# Sheet1.net
KiCad netlist of a schematic drawn in Altium Designer
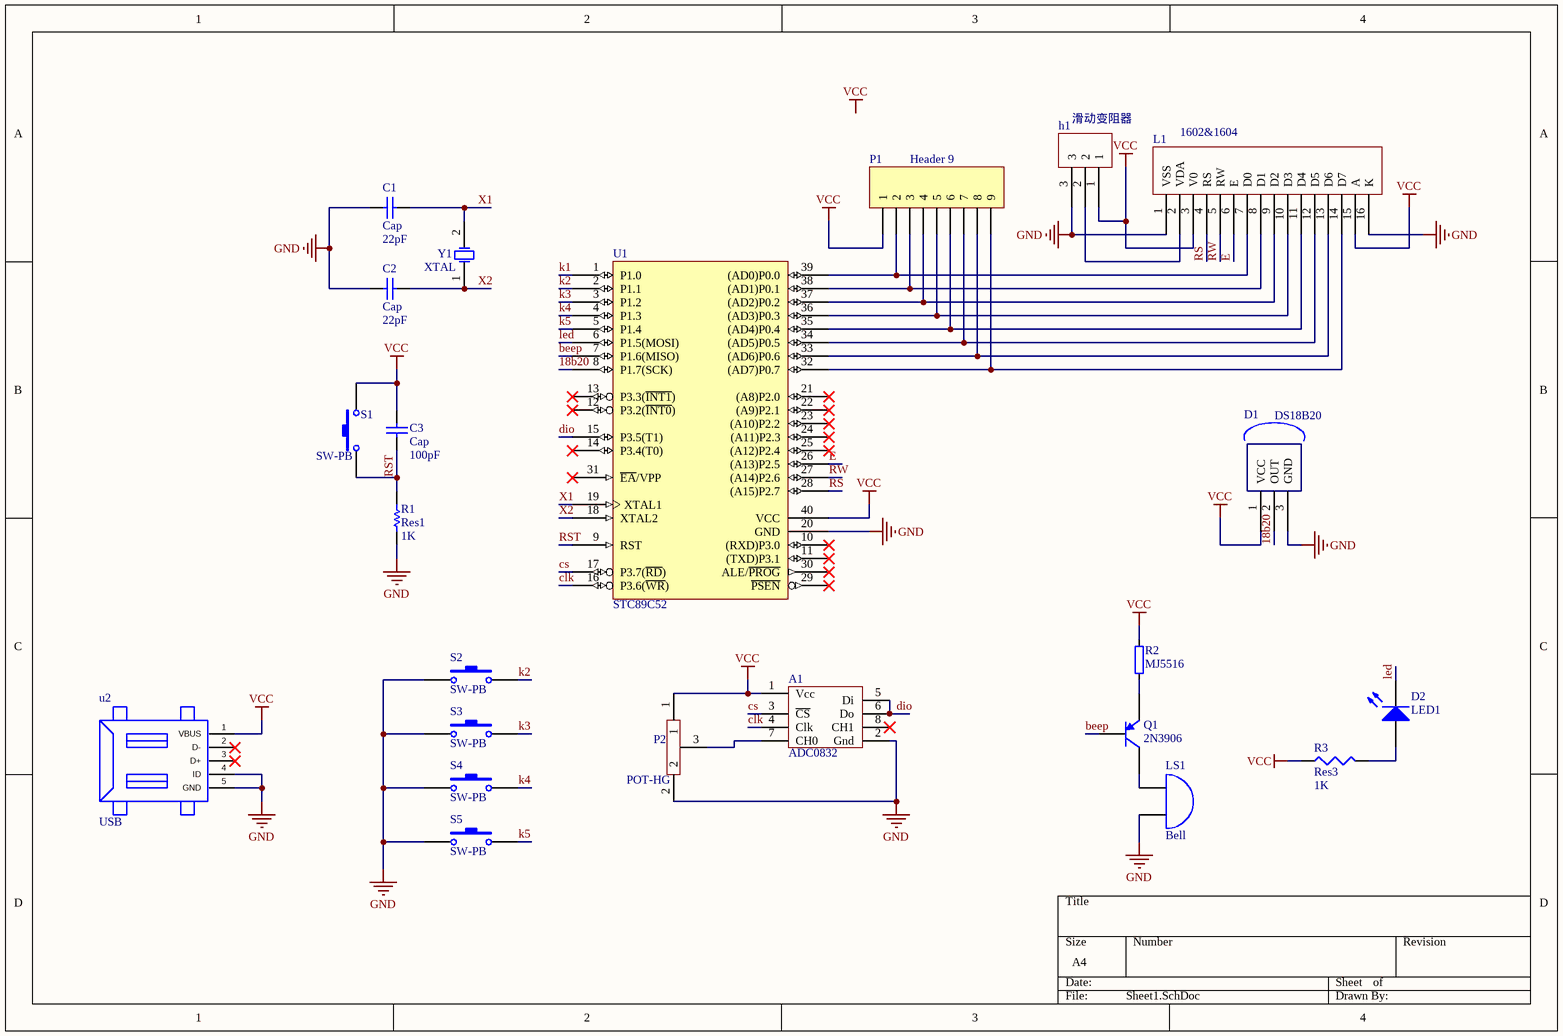
[diagram p0: Sheet1.SchDoc]

(export (version "E")
  (design (tool "Eeschema 10.0.6"))
  (components
    (comp (ref "A1") (value "ADC0832") (libsource (lib "mine") (part "ADC0832")))
    (comp (ref "C1")
      (value "Cap")
      (footprint "RAD-0.3")
      (description "Capacitor")
      (fields (field (name "ALTIUM_VALUE") "22pF") (field (name "PUBLISHER") "Altium Limited"))
      (libsource (lib "Miscellaneous Devices") (part "Cap"))
    )
    (comp (ref "C2")
      (value "Cap")
      (footprint "RAD-0.3")
      (description "Capacitor")
      (fields (field (name "ALTIUM_VALUE") "22pF") (field (name "PUBLISHER") "Altium Limited"))
      (libsource (lib "Miscellaneous Devices") (part "Cap"))
    )
    (comp (ref "C3")
      (value "Cap")
      (footprint "RAD-0.3")
      (description "Capacitor")
      (fields (field (name "ALTIUM_VALUE") "100pF") (field (name "PUBLISHER") "Altium Limited"))
      (libsource (lib "Miscellaneous Devices") (part "Cap"))
    )
    (comp (ref "D1") (value "DS18B20") (libsource (lib "mine") (part "DS18B20")))
    (comp (ref "D2")
      (value "LED1")
      (footprint "LED-1")
      (description "Typical RED GaAs LED")
      (fields (field (name "PUBLISHER") "Altium Limited"))
      (libsource (lib "Miscellaneous Devices") (part "LED1"))
    )
    (comp (ref "h1") (value "滑动变阻器") (libsource (lib "mine") (part "滑动变阻器")))
    (comp (ref "L1") (value "1602&1604") (libsource (lib "mine") (part "1602&1604")))
    (comp (ref "LS1")
      (value "Bell")
      (footprint "PIN2")
      (description "Electrical Bell")
      (fields (field (name "PUBLISHER") "Altium Limited"))
      (libsource (lib "Miscellaneous Devices") (part "Bell"))
    )
    (comp (ref "P1")
      (value "Header 9")
      (footprint "HDR1X9")
      (description "Header, 9-Pin")
      (fields (field (name "PUBLISHER") "Altium Limited"))
      (libsource (lib "Miscellaneous Connectors") (part "Header 9"))
    )
    (comp (ref "P2") (value "POT-HG") (libsource (lib "mine") (part "POT-HG")))
    (comp (ref "Q1")
      (value "2N3906")
      (footprint "TO-92A")
      (description "PNP General Purpose Amplifier")
      (fields (field (name "PUBLISHER") "Altium Limited"))
      (libsource (lib "Miscellaneous Devices") (part "2N3906"))
    )
    (comp (ref "R1")
      (value "Res1")
      (footprint "AXIAL-0.3")
      (description "Resistor")
      (fields (field (name "ALTIUM_VALUE") "1K") (field (name "PUBLISHER") "Altium Limited"))
      (libsource (lib "Miscellaneous Devices") (part "Res1"))
    )
    (comp (ref "R2")
      (value "MJ5516")
      (footprint "MJ5515")
      (description "CR-MJ5516")
      (libsource (lib "常用器件") (part "MJ5516"))
    )
    (comp (ref "R3")
      (value "Res3")
      (footprint "J1-0603")
      (description "Resistor")
      (fields (field (name "ALTIUM_VALUE") "1K") (field (name "PUBLISHER") "Altium Limited"))
      (libsource (lib "Miscellaneous Devices") (part "Res3"))
    )
    (comp (ref "S1")
      (value "SW-PB")
      (footprint "SPST-2")
      (description "Switch")
      (fields (field (name "PUBLISHER") "Altium Limited"))
      (libsource (lib "Miscellaneous Devices") (part "SW-PB"))
    )
    (comp (ref "S2")
      (value "SW-PB")
      (footprint "SPST-2")
      (description "Switch")
      (fields (field (name "PUBLISHER") "Altium Limited"))
      (libsource (lib "常用器件") (part "SW-PB"))
    )
    (comp (ref "S3")
      (value "SW-PB")
      (footprint "SPST-2")
      (description "Switch")
      (fields (field (name "PUBLISHER") "Altium Limited"))
      (libsource (lib "常用器件") (part "SW-PB"))
    )
    (comp (ref "S4")
      (value "SW-PB")
      (footprint "SPST-2")
      (description "Switch")
      (fields (field (name "PUBLISHER") "Altium Limited"))
      (libsource (lib "常用器件") (part "SW-PB"))
    )
    (comp (ref "S5")
      (value "SW-PB")
      (footprint "SPST-2")
      (description "Switch")
      (fields (field (name "PUBLISHER") "Altium Limited"))
      (libsource (lib "常用器件") (part "SW-PB"))
    )
    (comp (ref "U1")
      (value "STC89C52")
      (footprint "DIP-40")
      (description "8-Bit Microcontroller with 4K ISP Flash ROM")
      (libsource (lib "单片机8051") (part "AT89S51"))
    )
    (comp (ref "u2") (value "USB") (libsource (lib "mine") (part "USB")))
    (comp (ref "Y1")
      (value "XTAL")
      (footprint "R38")
      (description "Crystal Oscillator")
      (fields (field (name "PUBLISHER") "Altium Limited"))
      (libsource (lib "Miscellaneous Devices") (part "XTAL"))
    )
  )
  (nets
    (net (code "1") (name "/18b20") (class "Default")
      (node (ref "D1") (pin "2") (pinfunction "OUT_2") (pintype "passive"))
      (node (ref "U1") (pin "8") (pinfunction "P1.7(SCK)_8") (pintype "bidirectional"))
    )
    (net (code "2") (name "/E") (class "Default")
      (node (ref "L1") (pin "6") (pinfunction "E_6") (pintype "passive"))
      (node (ref "U1") (pin "26") (pinfunction "(A13)P2.5_26") (pintype "bidirectional"))
    )
    (net (code "3") (name "/RS") (class "Default")
      (node (ref "L1") (pin "4") (pinfunction "RS_4") (pintype "passive"))
      (node (ref "U1") (pin "28") (pinfunction "(A15)P2.7_28") (pintype "bidirectional"))
    )
    (net (code "4") (name "/RST") (class "Default")
      (node (ref "C3") (pin "1") (pinfunction "1_1") (pintype "passive"))
      (node (ref "R1") (pin "2") (pinfunction "2_2") (pintype "passive"))
      (node (ref "S1") (pin "1") (pinfunction "1_1") (pintype "passive"))
      (node (ref "U1") (pin "9") (pinfunction "RST_9") (pintype "input"))
    )
    (net (code "5") (name "/RW") (class "Default")
      (node (ref "L1") (pin "5") (pinfunction "RW_5") (pintype "passive"))
      (node (ref "U1") (pin "27") (pinfunction "(A14)P2.6_27") (pintype "bidirectional"))
    )
    (net (code "6") (name "/X1") (class "Default")
      (node (ref "C1") (pin "2") (pinfunction "2_2") (pintype "passive"))
      (node (ref "U1") (pin "19") (pinfunction "XTAL1_19") (pintype "input"))
      (node (ref "Y1") (pin "2") (pinfunction "OSC2_2") (pintype "passive"))
    )
    (net (code "7") (name "/X2") (class "Default")
      (node (ref "C2") (pin "2") (pinfunction "2_2") (pintype "passive"))
      (node (ref "U1") (pin "18") (pinfunction "XTAL2_18") (pintype "input"))
      (node (ref "Y1") (pin "1") (pinfunction "OSC1_1") (pintype "passive"))
    )
    (net (code "8") (name "/beep") (class "Default")
      (node (ref "Q1") (pin "2") (pinfunction "B_2") (pintype "passive"))
      (node (ref "U1") (pin "7") (pinfunction "P1.6(MISO)_7") (pintype "bidirectional"))
    )
    (net (code "9") (name "/clk") (class "Default")
      (node (ref "A1") (pin "4") (pinfunction "Clk_4") (pintype "passive"))
      (node (ref "U1") (pin "16") (pinfunction "P3.6(~{WR})_16") (pintype "bidirectional"))
    )
    (net (code "10") (name "/cs") (class "Default")
      (node (ref "A1") (pin "3") (pinfunction "~{CS}_3") (pintype "passive"))
      (node (ref "U1") (pin "17") (pinfunction "P3.7(~{RD})_17") (pintype "bidirectional"))
    )
    (net (code "11") (name "/dio") (class "Default")
      (node (ref "A1") (pin "5") (pinfunction "Di_5") (pintype "passive"))
      (node (ref "A1") (pin "6") (pinfunction "Do_6") (pintype "passive"))
      (node (ref "U1") (pin "15") (pinfunction "P3.5(T1)_15") (pintype "bidirectional"))
    )
    (net (code "12") (name "/k1") (class "Default")
      (node (ref "U1") (pin "1") (pinfunction "P1.0_1") (pintype "bidirectional"))
    )
    (net (code "13") (name "/k2") (class "Default")
      (node (ref "S2") (pin "2") (pinfunction "2_2") (pintype "passive"))
      (node (ref "U1") (pin "2") (pinfunction "P1.1_2") (pintype "bidirectional"))
    )
    (net (code "14") (name "/k3") (class "Default")
      (node (ref "S3") (pin "2") (pinfunction "2_2") (pintype "passive"))
      (node (ref "U1") (pin "3") (pinfunction "P1.2_3") (pintype "bidirectional"))
    )
    (net (code "15") (name "/k4") (class "Default")
      (node (ref "S4") (pin "2") (pinfunction "2_2") (pintype "passive"))
      (node (ref "U1") (pin "4") (pinfunction "P1.3_4") (pintype "bidirectional"))
    )
    (net (code "16") (name "/k5") (class "Default")
      (node (ref "S5") (pin "2") (pinfunction "2_2") (pintype "passive"))
      (node (ref "U1") (pin "5") (pinfunction "P1.4_5") (pintype "bidirectional"))
    )
    (net (code "17") (name "/led") (class "Default")
      (node (ref "D2") (pin "2") (pinfunction "K_2") (pintype "passive"))
      (node (ref "U1") (pin "6") (pinfunction "P1.5(MOSI)_6") (pintype "bidirectional"))
    )
    (net (code "18") (name "GND") (class "Default")
      (node (ref "A1") (pin "2") (pinfunction "Gnd_2") (pintype "passive"))
      (node (ref "C1") (pin "1") (pinfunction "1_1") (pintype "passive"))
      (node (ref "C2") (pin "1") (pinfunction "1_1") (pintype "passive"))
      (node (ref "D1") (pin "3") (pinfunction "GND_3") (pintype "passive"))
      (node (ref "L1") (pin "1") (pinfunction "VSS_1") (pintype "passive"))
      (node (ref "L1") (pin "16") (pinfunction "K_16") (pintype "passive"))
      (node (ref "LS1") (pin "2") (pinfunction "B_2") (pintype "passive"))
      (node (ref "P2") (pin "2") (pinfunction "2_2") (pintype "passive"))
      (node (ref "R1") (pin "1") (pinfunction "1_1") (pintype "passive"))
      (node (ref "S2") (pin "1") (pinfunction "1_1") (pintype "passive"))
      (node (ref "S3") (pin "1") (pinfunction "1_1") (pintype "passive"))
      (node (ref "S4") (pin "1") (pinfunction "1_1") (pintype "passive"))
      (node (ref "S5") (pin "1") (pinfunction "1_1") (pintype "passive"))
      (node (ref "U1") (pin "20") (pinfunction "GND_20") (pintype "power_in"))
      (node (ref "h1") (pin "3") (pinfunction "3_3") (pintype "passive"))
      (node (ref "u2") (pin "4") (pinfunction "ID_4") (pintype "passive"))
      (node (ref "u2") (pin "5") (pinfunction "GND_5") (pintype "passive"))
    )
    (net (code "19") (name "Net-(A1-CH0)") (class "Default")
      (node (ref "A1") (pin "7") (pinfunction "CH0_7") (pintype "passive"))
      (node (ref "P2") (pin "3") (pintype "passive"))
    )
    (net (code "20") (name "Net-(D2-A)") (class "Default")
      (node (ref "D2") (pin "1") (pinfunction "A_1") (pintype "passive"))
      (node (ref "R3") (pin "2") (pinfunction "2_2") (pintype "passive"))
    )
    (net (code "21") (name "Net-(L1-D0)") (class "Default")
      (node (ref "L1") (pin "7") (pinfunction "D0_7") (pintype "passive"))
      (node (ref "P1") (pin "2") (pinfunction "2_2") (pintype "passive"))
      (node (ref "U1") (pin "39") (pinfunction "(AD0)P0.0_39") (pintype "bidirectional"))
    )
    (net (code "22") (name "Net-(L1-D1)") (class "Default")
      (node (ref "L1") (pin "8") (pinfunction "D1_8") (pintype "passive"))
      (node (ref "P1") (pin "3") (pinfunction "3_3") (pintype "passive"))
      (node (ref "U1") (pin "38") (pinfunction "(AD1)P0.1_38") (pintype "bidirectional"))
    )
    (net (code "23") (name "Net-(L1-D2)") (class "Default")
      (node (ref "L1") (pin "9") (pinfunction "D2_9") (pintype "passive"))
      (node (ref "P1") (pin "4") (pinfunction "4_4") (pintype "passive"))
      (node (ref "U1") (pin "37") (pinfunction "(AD2)P0.2_37") (pintype "bidirectional"))
    )
    (net (code "24") (name "Net-(L1-D3)") (class "Default")
      (node (ref "L1") (pin "10") (pinfunction "D3_10") (pintype "passive"))
      (node (ref "P1") (pin "5") (pinfunction "5_5") (pintype "passive"))
      (node (ref "U1") (pin "36") (pinfunction "(AD3)P0.3_36") (pintype "bidirectional"))
    )
    (net (code "25") (name "Net-(L1-D4)") (class "Default")
      (node (ref "L1") (pin "11") (pinfunction "D4_11") (pintype "passive"))
      (node (ref "P1") (pin "6") (pinfunction "6_6") (pintype "passive"))
      (node (ref "U1") (pin "35") (pinfunction "(AD4)P0.4_35") (pintype "bidirectional"))
    )
    (net (code "26") (name "Net-(L1-D5)") (class "Default")
      (node (ref "L1") (pin "12") (pinfunction "D5_12") (pintype "passive"))
      (node (ref "P1") (pin "7") (pinfunction "7_7") (pintype "passive"))
      (node (ref "U1") (pin "34") (pinfunction "(AD5)P0.5_34") (pintype "bidirectional"))
    )
    (net (code "27") (name "Net-(L1-D6)") (class "Default")
      (node (ref "L1") (pin "13") (pinfunction "D6_13") (pintype "passive"))
      (node (ref "P1") (pin "8") (pinfunction "8_8") (pintype "passive"))
      (node (ref "U1") (pin "33") (pinfunction "(AD6)P0.6_33") (pintype "bidirectional"))
    )
    (net (code "28") (name "Net-(L1-D7)") (class "Default")
      (node (ref "L1") (pin "14") (pinfunction "D7_14") (pintype "passive"))
      (node (ref "P1") (pin "9") (pinfunction "9_9") (pintype "passive"))
      (node (ref "U1") (pin "32") (pinfunction "(AD7)P0.7_32") (pintype "bidirectional"))
    )
    (net (code "29") (name "Net-(L1-VDA)") (class "Default")
      (node (ref "L1") (pin "2") (pinfunction "VDA_2") (pintype "passive"))
      (node (ref "h1") (pin "2") (pinfunction "2_2") (pintype "passive"))
    )
    (net (code "30") (name "Net-(LS1-A)") (class "Default")
      (node (ref "LS1") (pin "1") (pinfunction "A_1") (pintype "passive"))
      (node (ref "Q1") (pin "3") (pinfunction "C_3") (pintype "passive"))
    )
    (net (code "31") (name "Net-(Q1-E)") (class "Default")
      (node (ref "Q1") (pin "1") (pinfunction "E_1") (pintype "passive"))
      (node (ref "R2") (pin "1") (pinfunction "1_1") (pintype "passive"))
    )
    (net (code "32") (name "VCC") (class "Default")
      (node (ref "A1") (pin "1") (pinfunction "Vcc_1") (pintype "passive"))
      (node (ref "C3") (pin "2") (pinfunction "2_2") (pintype "passive"))
      (node (ref "D1") (pin "1") (pinfunction "VCC_1") (pintype "passive"))
      (node (ref "L1") (pin "15") (pinfunction "A_15") (pintype "passive"))
      (node (ref "L1") (pin "3") (pinfunction "V0_3") (pintype "passive"))
      (node (ref "P1") (pin "1") (pinfunction "1_1") (pintype "passive"))
      (node (ref "P2") (pin "1") (pinfunction "1_1") (pintype "passive"))
      (node (ref "R2") (pin "2") (pinfunction "2_2") (pintype "passive"))
      (node (ref "R3") (pin "1") (pinfunction "1_1") (pintype "passive"))
      (node (ref "S1") (pin "2") (pinfunction "2_2") (pintype "passive"))
      (node (ref "U1") (pin "40") (pinfunction "VCC_40") (pintype "power_in"))
      (node (ref "h1") (pin "1") (pinfunction "1_1") (pintype "passive"))
      (node (ref "u2") (pin "1") (pinfunction "VBUS_1") (pintype "passive"))
    )
    (net (code "33") (name "unconnected-(A1-CH1-Pad8)") (class "Default")
      (node (ref "A1") (pin "8") (pinfunction "CH1_8") (pintype "passive+no_connect"))
    )
    (net (code "34") (name "unconnected-(U1-(A8)P2.0-Pad21)") (class "Default")
      (node (ref "U1") (pin "21") (pinfunction "(A8)P2.0_21") (pintype "bidirectional+no_connect"))
    )
    (net (code "35") (name "unconnected-(U1-(A9)P2.1-Pad22)") (class "Default")
      (node (ref "U1") (pin "22") (pinfunction "(A9)P2.1_22") (pintype "bidirectional+no_connect"))
    )
    (net (code "36") (name "unconnected-(U1-(A10)P2.2-Pad23)") (class "Default")
      (node (ref "U1") (pin "23") (pinfunction "(A10)P2.2_23") (pintype "bidirectional+no_connect"))
    )
    (net (code "37") (name "unconnected-(U1-(A11)P2.3-Pad24)") (class "Default")
      (node (ref "U1") (pin "24") (pinfunction "(A11)P2.3_24") (pintype "bidirectional+no_connect"))
    )
    (net (code "38") (name "unconnected-(U1-(A12)P2.4-Pad25)") (class "Default")
      (node (ref "U1") (pin "25") (pinfunction "(A12)P2.4_25") (pintype "bidirectional+no_connect"))
    )
    (net (code "39") (name "unconnected-(U1-(RXD)P3.0-Pad10)") (class "Default")
      (node (ref "U1") (pin "10") (pinfunction "(RXD)P3.0_10") (pintype "bidirectional+no_connect"))
    )
    (net (code "40") (name "unconnected-(U1-(TXD)P3.1-Pad11)") (class "Default")
      (node (ref "U1") (pin "11") (pinfunction "(TXD)P3.1_11") (pintype "bidirectional+no_connect"))
    )
    (net (code "41") (name "unconnected-(U1-ALE{slash}~{PROG}-Pad30)") (class "Default")
      (node (ref "U1") (pin "30") (pinfunction "ALE/~{PROG}_30") (pintype "output+no_connect"))
    )
    (net (code "42") (name "unconnected-(U1-P3.2(~{INT0})-Pad12)") (class "Default")
      (node (ref "U1") (pin "12") (pinfunction "P3.2(~{INT0})_12") (pintype "bidirectional+no_connect"))
    )
    (net (code "43") (name "unconnected-(U1-P3.3(~{INT1})-Pad13)") (class "Default")
      (node (ref "U1") (pin "13") (pinfunction "P3.3(~{INT1})_13") (pintype "bidirectional+no_connect"))
    )
    (net (code "44") (name "unconnected-(U1-P3.4(T0)-Pad14)") (class "Default")
      (node (ref "U1") (pin "14") (pinfunction "P3.4(T0)_14") (pintype "bidirectional+no_connect"))
    )
    (net (code "45") (name "unconnected-(U1-~{EA}{slash}VPP-Pad31)") (class "Default")
      (node (ref "U1") (pin "31") (pinfunction "~{EA}/VPP_31") (pintype "input+no_connect"))
    )
    (net (code "46") (name "unconnected-(U1-~{PSEN}-Pad29)") (class "Default")
      (node (ref "U1") (pin "29") (pinfunction "~{PSEN}_29") (pintype "output+no_connect"))
    )
    (net (code "47") (name "unconnected-(u2-D+-Pad3)") (class "Default")
      (node (ref "u2") (pin "3") (pinfunction "D+_3") (pintype "passive+no_connect"))
    )
    (net (code "48") (name "unconnected-(u2-D--Pad2)") (class "Default")
      (node (ref "u2") (pin "2") (pinfunction "D-_2") (pintype "passive+no_connect"))
    )
  )
)
